# Power.net
KiCad netlist of a schematic drawn in Altium Designer
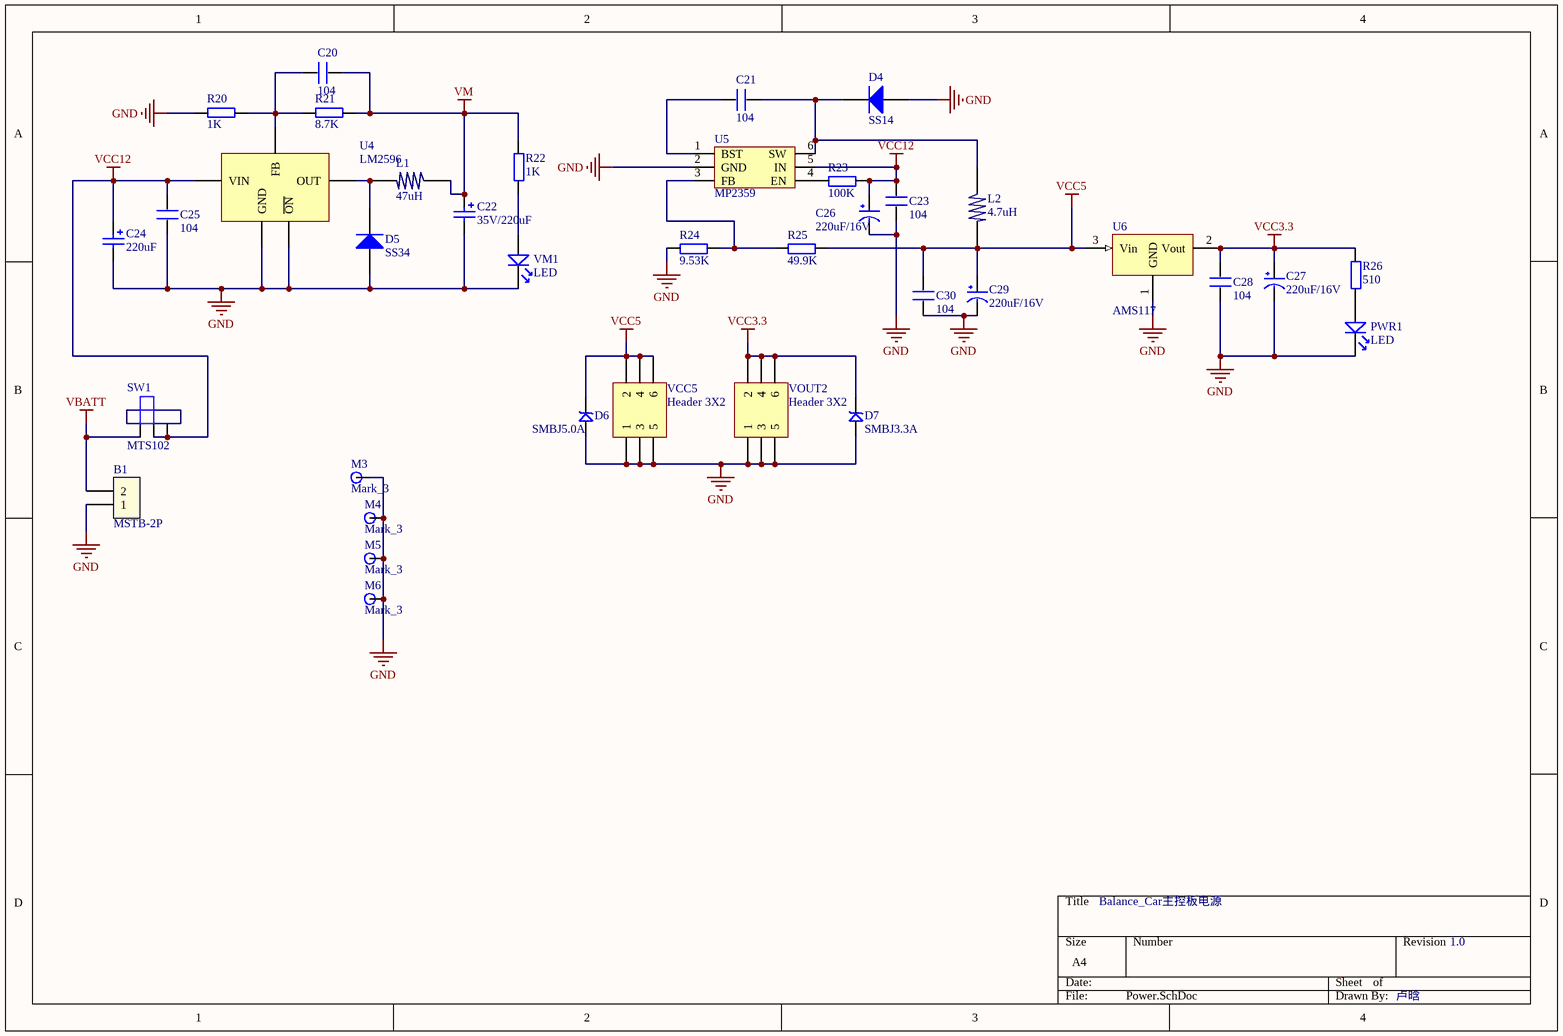
[diagram p0: Power.SchDoc]

(export (version "E")
  (design (tool "Eeschema 10.0.6"))
  (components
    (comp (ref "B1") (value "MSTB-2P") (footprint "MSTB-2P") (libsource (lib "3D库") (part "MSTB-2P")))
    (comp (ref "C20") (value "104") (footprint "0603C") (libsource (lib "WarShip V3 STM32103封装库") (part "C")))
    (comp (ref "C21") (value "104") (footprint "0603C") (libsource (lib "WarShip V3 STM32103封装库") (part "C")))
    (comp (ref "C22")
      (value "35V/220uF")
      (footprint "C_AUL-9.0*8.2")
      (description "Aluminum cap")
      (libsource (lib "3D库") (part "Cap_Alumi"))
    )
    (comp (ref "C23") (value "104") (footprint "0603C") (libsource (lib "WarShip V3 STM32103封装库") (part "C")))
    (comp (ref "C24")
      (value "220uF")
      (footprint "C_AUL-9.0*8.2")
      (description "Aluminum cap")
      (libsource (lib "3D库") (part "Cap_Alumi"))
    )
    (comp (ref "C25") (value "104") (footprint "0603C") (libsource (lib "WarShip V3 STM32103封装库") (part "C")))
    (comp (ref "C26")
      (value "220uF/16V")
      (footprint "C_AUL-6.6*7")
      (libsource (lib "WarShip V3 STM32103封装库") (part "CAP"))
    )
    (comp (ref "C27")
      (value "220uF/16V")
      (footprint "C_AUL-6.6*7")
      (libsource (lib "WarShip V3 STM32103封装库") (part "CAP"))
    )
    (comp (ref "C28") (value "104") (footprint "0603C") (libsource (lib "WarShip V3 STM32103封装库") (part "C")))
    (comp (ref "C29")
      (value "220uF/16V")
      (footprint "C_AUL-6.6*7")
      (libsource (lib "WarShip V3 STM32103封装库") (part "CAP"))
    )
    (comp (ref "C30") (value "104") (footprint "0603C") (libsource (lib "WarShip V3 STM32103封装库") (part "C")))
    (comp (ref "D4")
      (value "SS14")
      (footprint "SMA/DO-214AC")
      (description "Default Diode")
      (fields (field (name "PUBLISHER") "Altium Limited"))
      (libsource (lib "3D库") (part "Diode"))
    )
    (comp (ref "D5")
      (value "SS34")
      (footprint "SMB/DO-214AA")
      (description "Default Diode")
      (fields (field (name "PUBLISHER") "Altium Limited"))
      (libsource (lib "3D库") (part "Diode"))
    )
    (comp (ref "D6")
      (value "SMBJ5.0A")
      (footprint "SMB/DO-214AA")
      (description "TVS")
      (libsource (lib "WarShip V3 STM32103封装库") (part "SMBJ"))
    )
    (comp (ref "D7")
      (value "SMBJ3.3A")
      (footprint "SMB/DO-214AA")
      (description "TVS")
      (libsource (lib "WarShip V3 STM32103封装库") (part "SMBJ"))
    )
    (comp (ref "L1") (value "47uH") (footprint "CDRH127") (libsource (lib "3D库") (part "L")))
    (comp (ref "L2") (value "4.7uH") (footprint "CDRH74") (libsource (lib "") (part "L_1")))
    (comp (ref "M3")
      (value "Mark_3")
      (footprint "Mark3")
      (description "3mm安装孔")
      (libsource (lib "3D库") (part "Mark_3"))
    )
    (comp (ref "M4")
      (value "Mark_3")
      (footprint "Mark3")
      (description "3mm安装孔")
      (libsource (lib "3D库") (part "Mark_3"))
    )
    (comp (ref "M5")
      (value "Mark_3")
      (footprint "Mark3")
      (description "3mm安装孔")
      (libsource (lib "3D库") (part "Mark_3"))
    )
    (comp (ref "M6")
      (value "Mark_3")
      (footprint "Mark3")
      (description "3mm安装孔")
      (libsource (lib "3D库") (part "Mark_3"))
    )
    (comp (ref "PWR1") (value "LED") (footprint "0603D-R") (libsource (lib "STM32F429核心板封装库") (part "LED")))
    (comp (ref "R20") (value "1K") (footprint "0603R") (libsource (lib "WarShip V3 STM32103封装库") (part "R")))
    (comp (ref "R21")
      (value "8.7K")
      (footprint "0603R")
      (libsource (lib "WarShip V3 STM32103封装库") (part "R"))
    )
    (comp (ref "R22") (value "1K") (footprint "0603R") (libsource (lib "STM32F429核心板封装库") (part "R")))
    (comp (ref "R23")
      (value "100K")
      (footprint "0603R")
      (libsource (lib "WarShip V3 STM32103封装库") (part "R"))
    )
    (comp (ref "R24")
      (value "9.53K")
      (footprint "0603R")
      (libsource (lib "WarShip V3 STM32103封装库") (part "R"))
    )
    (comp (ref "R25")
      (value "49.9K")
      (footprint "0603R")
      (libsource (lib "WarShip V3 STM32103封装库") (part "R"))
    )
    (comp (ref "R26") (value "510") (footprint "0603R") (libsource (lib "STM32F429核心板封装库") (part "R")))
    (comp (ref "SW1") (value "MTS102") (footprint "MTS102") (libsource (lib "3D库") (part "MTS102")))
    (comp (ref "U4") (value "LM2596") (footprint "TO-263-5") (libsource (lib "3D库") (part "LM2596")))
    (comp (ref "U5")
      (value "MP2359")
      (footprint "SOT23-6L(PITCH 0.95)")
      (description "DC DC Step Down IC")
      (libsource (lib "3D库") (part "MP2359"))
    )
    (comp (ref "U6") (value "AMS117") (footprint "SOT-223") (libsource (lib "3D库") (part "AMS1117")))
    (comp (ref "VCC5")
      (value "Header 3X2")
      (footprint "Miscellaneous Connectors:HDR2X3")
      (description "Header, 3-Pin, Dual row")
      (fields (field (name "PUBLISHER") "Altium Limited"))
      (libsource (lib "WarShip V3 STM32103封装库") (part "Header 3X2"))
    )
    (comp (ref "VM1") (value "LED") (footprint "0603D-R") (libsource (lib "STM32F429核心板封装库") (part "LED")))
    (comp (ref "VOUT2")
      (value "Header 3X2")
      (footprint "HDR2X3")
      (description "Header, 3-Pin, Dual row")
      (fields (field (name "PUBLISHER") "Altium Limited"))
      (libsource (lib "WarShip V3 STM32103封装库") (part "Header 3X2"))
    )
  )
  (nets
    (net (code "1") (name "GND") (class "Default")
      (node (ref "B1") (pin "1") (pinfunction "1_1") (pintype "passive"))
      (node (ref "C22") (pin "2") (pinfunction "2_2") (pintype "passive"))
      (node (ref "C23") (pin "1") (pintype "passive"))
      (node (ref "C24") (pin "2") (pinfunction "2_2") (pintype "passive"))
      (node (ref "C25") (pin "1") (pintype "passive"))
      (node (ref "C26") (pin "2") (pinfunction "GND_2") (pintype "passive"))
      (node (ref "C27") (pin "2") (pinfunction "GND_2") (pintype "passive"))
      (node (ref "C28") (pin "1") (pintype "passive"))
      (node (ref "C29") (pin "2") (pinfunction "GND_2") (pintype "passive"))
      (node (ref "C30") (pin "1") (pintype "passive"))
      (node (ref "D4") (pin "1") (pinfunction "A_1") (pintype "passive"))
      (node (ref "D5") (pin "1") (pinfunction "A_1") (pintype "passive"))
      (node (ref "D6") (pin "1") (pintype "passive"))
      (node (ref "D7") (pin "1") (pintype "passive"))
      (node (ref "M3") (pin "1") (pinfunction "1_1") (pintype "passive"))
      (node (ref "M4") (pin "1") (pinfunction "1_1") (pintype "passive"))
      (node (ref "M5") (pin "1") (pinfunction "1_1") (pintype "passive"))
      (node (ref "M6") (pin "1") (pinfunction "1_1") (pintype "passive"))
      (node (ref "PWR1") (pin "2") (pinfunction "2_2") (pintype "passive"))
      (node (ref "R20") (pin "2") (pintype "passive"))
      (node (ref "R24") (pin "1") (pintype "passive"))
      (node (ref "U4") (pin "3") (pinfunction "GND_3") (pintype "power_in"))
      (node (ref "U4") (pin "5") (pinfunction "~{ON}_5") (pintype "passive"))
      (node (ref "U5") (pin "2") (pinfunction "GND_2") (pintype "passive"))
      (node (ref "U6") (pin "1") (pinfunction "GND_1") (pintype "passive"))
      (node (ref "VCC5") (pin "1") (pinfunction "1_1") (pintype "passive"))
      (node (ref "VCC5") (pin "3") (pinfunction "3_3") (pintype "passive"))
      (node (ref "VCC5") (pin "5") (pinfunction "5_5") (pintype "passive"))
      (node (ref "VM1") (pin "2") (pinfunction "2_2") (pintype "passive"))
      (node (ref "VOUT2") (pin "1") (pinfunction "1_1") (pintype "passive"))
      (node (ref "VOUT2") (pin "3") (pinfunction "3_3") (pintype "passive"))
      (node (ref "VOUT2") (pin "5") (pinfunction "5_5") (pintype "passive"))
    )
    (net (code "2") (name "Net-(D4-K)") (class "Default")
      (node (ref "C21") (pin "2") (pintype "passive"))
      (node (ref "D4") (pin "2") (pinfunction "K_2") (pintype "passive"))
      (node (ref "L2") (pin "2") (pinfunction "2_2") (pintype "passive"))
      (node (ref "U5") (pin "6") (pinfunction "SW_6") (pintype "passive"))
    )
    (net (code "3") (name "Net-(D5-K)") (class "Default")
      (node (ref "D5") (pin "2") (pinfunction "K_2") (pintype "passive"))
      (node (ref "L1") (pin "1") (pinfunction "1_1") (pintype "passive"))
      (node (ref "U4") (pin "2") (pinfunction "OUT_2") (pintype "power_in"))
    )
    (net (code "4") (name "Net-(PWR1-Pad1)") (class "Default")
      (node (ref "PWR1") (pin "1") (pinfunction "1_1") (pintype "passive"))
      (node (ref "R26") (pin "1") (pintype "passive"))
    )
    (net (code "5") (name "Net-(R22-Pad1)") (class "Default")
      (node (ref "R22") (pin "1") (pintype "passive"))
      (node (ref "VM1") (pin "1") (pinfunction "1_1") (pintype "passive"))
    )
    (net (code "6") (name "Net-(U4-FB)") (class "Default")
      (node (ref "C20") (pin "2") (pintype "passive"))
      (node (ref "R20") (pin "1") (pintype "passive"))
      (node (ref "R21") (pin "2") (pintype "passive"))
      (node (ref "U4") (pin "4") (pinfunction "FB_4") (pintype "passive"))
    )
    (net (code "7") (name "Net-(U5-BST)") (class "Default")
      (node (ref "C21") (pin "1") (pintype "passive"))
      (node (ref "U5") (pin "1") (pinfunction "BST_1") (pintype "passive"))
    )
    (net (code "8") (name "Net-(U5-EN)") (class "Default")
      (node (ref "R23") (pin "1") (pintype "passive"))
      (node (ref "U5") (pin "4") (pinfunction "EN_4") (pintype "passive"))
    )
    (net (code "9") (name "Net-(U5-FB)") (class "Default")
      (node (ref "R24") (pin "2") (pintype "passive"))
      (node (ref "R25") (pin "1") (pintype "passive"))
      (node (ref "U5") (pin "3") (pinfunction "FB_3") (pintype "passive"))
    )
    (net (code "10") (name "VBATT") (class "Default")
      (node (ref "B1") (pin "2") (pinfunction "2_2") (pintype "passive"))
      (node (ref "SW1") (pin "1") (pinfunction "1_1") (pintype "passive"))
    )
    (net (code "11") (name "VCC3.3") (class "Default")
      (node (ref "C27") (pin "1") (pinfunction "VCC_1") (pintype "passive"))
      (node (ref "C28") (pin "2") (pintype "passive"))
      (node (ref "D7") (pin "2") (pintype "passive"))
      (node (ref "R26") (pin "2") (pintype "passive"))
      (node (ref "U6") (pin "2") (pinfunction "Vout_2") (pintype "power_in"))
      (node (ref "VOUT2") (pin "2") (pinfunction "2_2") (pintype "passive"))
      (node (ref "VOUT2") (pin "4") (pinfunction "4_4") (pintype "passive"))
      (node (ref "VOUT2") (pin "6") (pinfunction "6_6") (pintype "passive"))
    )
    (net (code "12") (name "VCC5") (class "Default")
      (node (ref "C29") (pin "1") (pinfunction "VCC_1") (pintype "passive"))
      (node (ref "C30") (pin "2") (pintype "passive"))
      (node (ref "D6") (pin "2") (pintype "passive"))
      (node (ref "L2") (pin "1") (pinfunction "1_1") (pintype "passive"))
      (node (ref "R25") (pin "2") (pintype "passive"))
      (node (ref "U6") (pin "3") (pinfunction "Vin_3") (pintype "input"))
      (node (ref "VCC5") (pin "2") (pinfunction "2_2") (pintype "passive"))
      (node (ref "VCC5") (pin "4") (pinfunction "4_4") (pintype "passive"))
      (node (ref "VCC5") (pin "6") (pinfunction "6_6") (pintype "passive"))
    )
    (net (code "13") (name "VCC12") (class "Default")
      (node (ref "C23") (pin "2") (pintype "passive"))
      (node (ref "C24") (pin "1") (pinfunction "1_1") (pintype "passive"))
      (node (ref "C25") (pin "2") (pintype "passive"))
      (node (ref "C26") (pin "1") (pinfunction "VCC_1") (pintype "passive"))
      (node (ref "R23") (pin "2") (pintype "passive"))
      (node (ref "SW1") (pin "2") (pinfunction "2_2") (pintype "passive"))
      (node (ref "SW1") (pin "3") (pinfunction "3_3") (pintype "passive"))
      (node (ref "U4") (pin "1") (pinfunction "VIN_1") (pintype "power_in"))
      (node (ref "U5") (pin "5") (pinfunction "IN_5") (pintype "passive"))
    )
    (net (code "14") (name "VM") (class "Default")
      (node (ref "C20") (pin "1") (pintype "passive"))
      (node (ref "C22") (pin "1") (pinfunction "1_1") (pintype "passive"))
      (node (ref "L1") (pin "2") (pinfunction "2_2") (pintype "passive"))
      (node (ref "R21") (pin "1") (pintype "passive"))
      (node (ref "R22") (pin "2") (pintype "passive"))
    )
  )
)
